# avr_ring2_v1_1.net
KiCad netlist of a schematic drawn in EAGLE
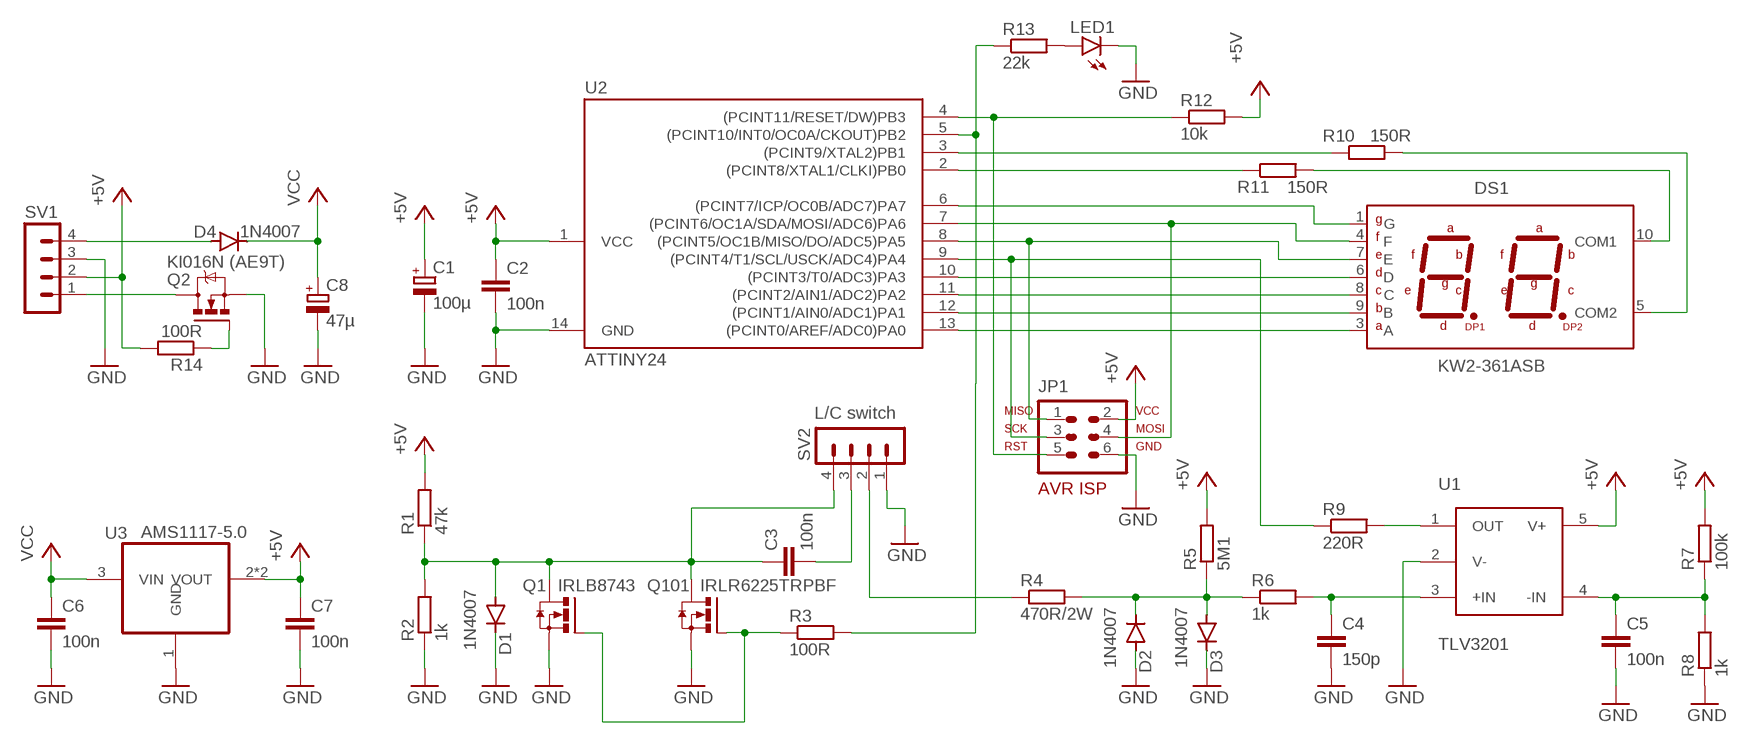
[diagram p0: schematic, sheet 1]

(export (version "E")
  (design (tool "Eeschema 10.0.6"))
  (components
    (comp (ref "C1")
      (value "100µ")
      (footprint "eagle-import:E2,5-5")
      (libsource (lib "eagle-import") (part "CPOL-EUE2.5-5"))
    )
    (comp (ref "C2")
      (value "100n")
      (footprint "eagle-import:C1206")
      (libsource (lib "eagle-import") (part "C-EUC1206"))
    )
    (comp (ref "C3")
      (value "100n")
      (footprint "eagle-import:C102_152-062X184")
      (libsource (lib "eagle-import") (part "C-EU102_152-062X184"))
    )
    (comp (ref "C4")
      (value "150p")
      (footprint "eagle-import:C1206")
      (libsource (lib "eagle-import") (part "C-EUC1206"))
    )
    (comp (ref "C5")
      (value "100n")
      (footprint "eagle-import:C1206")
      (libsource (lib "eagle-import") (part "C-EUC1206"))
    )
    (comp (ref "C6")
      (value "100n")
      (footprint "eagle-import:C1206")
      (libsource (lib "eagle-import") (part "C-EUC1206"))
    )
    (comp (ref "C7")
      (value "100n")
      (footprint "eagle-import:C1206")
      (libsource (lib "eagle-import") (part "C-EUC1206"))
    )
    (comp (ref "C8")
      (value "47µ")
      (footprint "eagle-import:E2,5-5")
      (libsource (lib "eagle-import") (part "CPOL-EUE2.5-5"))
    )
    (comp (ref "D1")
      (value "1N4007")
      (footprint "eagle-import:DO214AC")
      (libsource (lib "eagle-import") (part "DIODE-DO214AC"))
    )
    (comp (ref "D2")
      (value "1N4007")
      (footprint "eagle-import:DO214AC")
      (libsource (lib "eagle-import") (part "DIODE-DO214AC"))
    )
    (comp (ref "D3")
      (value "1N4007")
      (footprint "eagle-import:DO214AC")
      (libsource (lib "eagle-import") (part "DIODE-DO214AC"))
    )
    (comp (ref "D4")
      (value "1N4007")
      (footprint "eagle-import:DO214AC")
      (libsource (lib "eagle-import") (part "DIODE-DO214AC"))
    )
    (comp (ref "DS1")
      (value "KW2-361ASB")
      (footprint "eagle-import:DA03-11SURKWA")
      (fields (field (name "MANUFACTURER") "Kingbright") (field (name "MPN") "DA03-11SURKWA"))
      (libsource (lib "eagle-import") (part "DA03-11SUR-GA"))
    )
    (comp (ref "JP1")
      (value "AVR-ISP")
      (footprint "eagle-import:AVR-ISP-6")
      (libsource (lib "eagle-import") (part "AVR-ISP-6VERT"))
    )
    (comp (ref "LED1")
      (value "LED3MM")
      (footprint "eagle-import:LED3MM")
      (libsource (lib "eagle-import") (part "LED3MM"))
    )
    (comp (ref "Q1")
      (value "IRLB8743")
      (footprint "eagle-import:TO220AH")
      (libsource (lib "eagle-import") (part "IRF3704"))
    )
    (comp (ref "Q2")
      (value "KI016N (AE9T)")
      (footprint "eagle-import:SOT23")
      (libsource (lib "eagle-import") (part "NMOSFETSOT23-GSD_"))
    )
    (comp (ref "Q101")
      (value "IRLR6225TRPBF")
      (footprint "eagle-import:TO-252-3")
      (libsource (lib "eagle-import") (part "IRLR6225TRPBF"))
    )
    (comp (ref "R1")
      (value "47k")
      (footprint "eagle-import:R1206")
      (libsource (lib "eagle-import") (part "R-EU_R1206"))
    )
    (comp (ref "R2")
      (value "1k")
      (footprint "eagle-import:R1206")
      (libsource (lib "eagle-import") (part "R-EU_R1206"))
    )
    (comp (ref "R3")
      (value "100R")
      (footprint "eagle-import:R1206")
      (libsource (lib "eagle-import") (part "R-EU_R1206"))
    )
    (comp (ref "R4")
      (value "470R/2W")
      (footprint "eagle-import:0414_15")
      (libsource (lib "eagle-import") (part "R-EU_0414/15"))
    )
    (comp (ref "R5")
      (value "5M1")
      (footprint "eagle-import:R1206")
      (libsource (lib "eagle-import") (part "R-EU_R1206"))
    )
    (comp (ref "R6")
      (value "1k")
      (footprint "eagle-import:R1206")
      (libsource (lib "eagle-import") (part "R-EU_R1206"))
    )
    (comp (ref "R7")
      (value "100k")
      (footprint "eagle-import:R1206")
      (libsource (lib "eagle-import") (part "R-EU_R1206"))
    )
    (comp (ref "R8")
      (value "1k")
      (footprint "eagle-import:R1206")
      (libsource (lib "eagle-import") (part "R-EU_R1206"))
    )
    (comp (ref "R9")
      (value "220R")
      (footprint "eagle-import:R1206")
      (libsource (lib "eagle-import") (part "R-EU_R1206"))
    )
    (comp (ref "R10")
      (value "150R")
      (footprint "eagle-import:R1206")
      (libsource (lib "eagle-import") (part "R-EU_R1206"))
    )
    (comp (ref "R11")
      (value "150R")
      (footprint "eagle-import:R1206")
      (libsource (lib "eagle-import") (part "R-EU_R1206"))
    )
    (comp (ref "R12")
      (value "10k")
      (footprint "eagle-import:R1206")
      (libsource (lib "eagle-import") (part "R-EU_R1206"))
    )
    (comp (ref "R13")
      (value "22k")
      (footprint "eagle-import:R1206")
      (libsource (lib "eagle-import") (part "R-EU_R1206"))
    )
    (comp (ref "R14")
      (value "100R")
      (footprint "eagle-import:R1206")
      (libsource (lib "eagle-import") (part "R-EU_R1206"))
    )
    (comp (ref "SV1")
      (value "MA04-1")
      (footprint "eagle-import:MA04-1")
      (libsource (lib "eagle-import") (part "MA04-1"))
    )
    (comp (ref "SV2")
      (value "L/C switch")
      (footprint "eagle-import:MA04-1")
      (libsource (lib "eagle-import") (part "MA04-1"))
    )
    (comp (ref "U1")
      (value "TLV3201")
      (footprint "eagle-import:SOT-23-5")
      (fields
        (field (name "DIGIKEY_PART_NUMBER") "296-19546-1-ND")
        (field (name "MANUFACTURER") "Texas Instruments")
        (field (name "MPN") "OPA333AIDBVT")
        (field (name "CREATED") "PCBLayout.com")
      )
      (libsource (lib "eagle-import") (part "OPA333AIDBVT"))
    )
    (comp (ref "U2")
      (value "ATTINY24")
      (footprint "eagle-import:SOIC14")
      (libsource (lib "eagle-import") (part "TINY24/44/84-SSU"))
    )
    (comp (ref "U3")
      (value "AMS1117-5.0")
      (footprint "eagle-import:SOT223")
      (fields (field (name "MPN") "REG1117"))
      (libsource (lib "eagle-import") (part "REG1117"))
    )
  )
  (nets
    (net (code "1") (name "+5V") (class "Default")
      (node (ref "C1") (pin "+") (pinfunction "+_+") (pintype "passive"))
      (node (ref "C2") (pin "1") (pinfunction "1_1") (pintype "passive"))
      (node (ref "C7") (pin "1") (pinfunction "1_1") (pintype "passive"))
      (node (ref "JP1") (pin "2") (pinfunction "2_2") (pintype "passive"))
      (node (ref "R1") (pin "2") (pinfunction "2_2") (pintype "passive"))
      (node (ref "R12") (pin "2") (pinfunction "2_2") (pintype "passive"))
      (node (ref "R14") (pin "2") (pinfunction "2_2") (pintype "passive"))
      (node (ref "R5") (pin "2") (pinfunction "2_2") (pintype "passive"))
      (node (ref "R7") (pin "2") (pinfunction "2_2") (pintype "passive"))
      (node (ref "SV1") (pin "2") (pinfunction "2_2") (pintype "passive"))
      (node (ref "U1") (pin "5") (pinfunction "V+_5") (pintype "power_in"))
      (node (ref "U2") (pin "1") (pinfunction "VCC_1") (pintype "power_in"))
      (node (ref "U3") (pin "2") (pinfunction "VOUT_2") (pintype "output"))
      (node (ref "U3") (pin "4") (pinfunction "VOUT_4") (pintype "output"))
    )
    (net (code "2") (name "GND") (class "Default")
      (node (ref "C1") (pin "-") (pinfunction "-_-") (pintype "passive"))
      (node (ref "C2") (pin "2") (pinfunction "2_2") (pintype "passive"))
      (node (ref "C4") (pin "2") (pinfunction "2_2") (pintype "passive"))
      (node (ref "C5") (pin "2") (pinfunction "2_2") (pintype "passive"))
      (node (ref "C6") (pin "2") (pinfunction "2_2") (pintype "passive"))
      (node (ref "C7") (pin "2") (pinfunction "2_2") (pintype "passive"))
      (node (ref "C8") (pin "-") (pinfunction "-_-") (pintype "passive"))
      (node (ref "D1") (pin "C") (pinfunction "C_C") (pintype "passive"))
      (node (ref "D2") (pin "A") (pinfunction "A_A") (pintype "passive"))
      (node (ref "D3") (pin "C") (pinfunction "C_C") (pintype "passive"))
      (node (ref "JP1") (pin "6") (pinfunction "6_6") (pintype "passive"))
      (node (ref "LED1") (pin "K") (pinfunction "C_K") (pintype "passive"))
      (node (ref "Q1") (pin "E") (pinfunction "S_E") (pintype "passive"))
      (node (ref "Q101") (pin "2") (pinfunction "S_2") (pintype "passive"))
      (node (ref "Q2") (pin "2") (pinfunction "S_2") (pintype "passive"))
      (node (ref "R2") (pin "1") (pinfunction "1_1") (pintype "passive"))
      (node (ref "R8") (pin "1") (pinfunction "1_1") (pintype "passive"))
      (node (ref "SV1") (pin "3") (pinfunction "3_3") (pintype "passive"))
      (node (ref "SV2") (pin "1") (pinfunction "1_1") (pintype "passive"))
      (node (ref "U1") (pin "2") (pinfunction "V-_2") (pintype "power_in"))
      (node (ref "U2") (pin "14") (pinfunction "GND_14") (pintype "power_in"))
      (node (ref "U3") (pin "1") (pinfunction "GND_1") (pintype "power_in"))
    )
    (net (code "3") (name "Net-(C3-2-Pad3)") (class "Default")
      (node (ref "C3") (pin "2") (pinfunction "2_2") (pintype "passive"))
      (node (ref "C3") (pin "3") (pinfunction "2_3") (pintype "passive"))
      (node (ref "SV2") (pin "3") (pinfunction "3_3") (pintype "passive"))
    )
    (net (code "4") (name "Net-(D2-PadC)") (class "Default")
      (node (ref "D2") (pin "C") (pinfunction "C_C") (pintype "passive"))
      (node (ref "D3") (pin "A") (pinfunction "A_A") (pintype "passive"))
      (node (ref "R4") (pin "2") (pinfunction "2_2") (pintype "passive"))
      (node (ref "R5") (pin "1") (pinfunction "1_1") (pintype "passive"))
      (node (ref "R6") (pin "1") (pinfunction "1_1") (pintype "passive"))
    )
    (net (code "5") (name "Net-(D4-PadA)") (class "Default")
      (node (ref "D4") (pin "A") (pinfunction "A_A") (pintype "passive"))
      (node (ref "SV1") (pin "4") (pinfunction "4_4") (pintype "passive"))
    )
    (net (code "6") (name "Net-(DS1-A)") (class "Default")
      (node (ref "DS1") (pin "3") (pinfunction "A_3") (pintype "passive"))
      (node (ref "U2") (pin "13") (pinfunction "(PCINT0/AREF/ADC0)PA0_13") (pintype "bidirectional"))
    )
    (net (code "7") (name "Net-(DS1-B)") (class "Default")
      (node (ref "DS1") (pin "9") (pinfunction "B_9") (pintype "passive"))
      (node (ref "U2") (pin "12") (pinfunction "(PCINT1/AIN0/ADC1)PA1_12") (pintype "bidirectional"))
    )
    (net (code "8") (name "Net-(DS1-C)") (class "Default")
      (node (ref "DS1") (pin "8") (pinfunction "C_8") (pintype "passive"))
      (node (ref "U2") (pin "11") (pinfunction "(PCINT2/AIN1/ADC2)PA2_11") (pintype "bidirectional"))
    )
    (net (code "9") (name "Net-(DS1-COM1)") (class "Default")
      (node (ref "DS1") (pin "10") (pinfunction "COM1_10") (pintype "passive"))
      (node (ref "R11") (pin "2") (pinfunction "2_2") (pintype "passive"))
    )
    (net (code "10") (name "Net-(DS1-COM2)") (class "Default")
      (node (ref "DS1") (pin "5") (pinfunction "COM2_5") (pintype "passive"))
      (node (ref "R10") (pin "2") (pinfunction "2_2") (pintype "passive"))
    )
    (net (code "11") (name "Net-(DS1-D)") (class "Default")
      (node (ref "DS1") (pin "6") (pinfunction "D_6") (pintype "passive"))
      (node (ref "U2") (pin "10") (pinfunction "(PCINT3/T0/ADC3)PA3_10") (pintype "bidirectional"))
    )
    (net (code "12") (name "Net-(DS1-E)") (class "Default")
      (node (ref "DS1") (pin "7") (pinfunction "E_7") (pintype "passive"))
      (node (ref "JP1") (pin "1") (pinfunction "1_1") (pintype "passive"))
      (node (ref "U2") (pin "8") (pinfunction "(PCINT5/OC1B/MISO/DO/ADC5)PA5_8") (pintype "bidirectional"))
    )
    (net (code "13") (name "Net-(DS1-F)") (class "Default")
      (node (ref "DS1") (pin "4") (pinfunction "F_4") (pintype "passive"))
      (node (ref "JP1") (pin "4") (pinfunction "4_4") (pintype "passive"))
      (node (ref "U2") (pin "7") (pinfunction "(PCINT6/OC1A/SDA/MOSI/ADC6)PA6_7") (pintype "bidirectional"))
    )
    (net (code "14") (name "Net-(DS1-G)") (class "Default")
      (node (ref "DS1") (pin "1") (pinfunction "G_1") (pintype "passive"))
      (node (ref "U2") (pin "6") (pinfunction "(PCINT7/ICP/OC0B/ADC7)PA7_6") (pintype "bidirectional"))
    )
    (net (code "15") (name "Net-(LED1-PadA)") (class "Default")
      (node (ref "LED1") (pin "A") (pinfunction "A_A") (pintype "passive"))
      (node (ref "R13") (pin "2") (pinfunction "2_2") (pintype "passive"))
    )
    (net (code "16") (name "Net-(Q1-D)") (class "Default")
      (node (ref "C3") (pin "1") (pinfunction "1_1") (pintype "passive"))
      (node (ref "D1") (pin "A") (pinfunction "A_A") (pintype "passive"))
      (node (ref "Q1") (pin "C") (pinfunction "D_C") (pintype "passive"))
      (node (ref "Q101") (pin "3") (pinfunction "D_3") (pintype "passive"))
      (node (ref "R1") (pin "1") (pinfunction "1_1") (pintype "passive"))
      (node (ref "R2") (pin "2") (pinfunction "2_2") (pintype "passive"))
      (node (ref "SV2") (pin "4") (pinfunction "4_4") (pintype "passive"))
    )
    (net (code "17") (name "Net-(Q1-G)") (class "Default")
      (node (ref "Q1") (pin "B") (pinfunction "G_B") (pintype "passive"))
      (node (ref "Q101") (pin "1") (pinfunction "G_1") (pintype "passive"))
      (node (ref "R3") (pin "1") (pinfunction "1_1") (pintype "passive"))
    )
    (net (code "18") (name "Net-(Q2-D)") (class "Default")
      (node (ref "Q2") (pin "3") (pinfunction "D_3") (pintype "passive"))
      (node (ref "SV1") (pin "1") (pinfunction "1_1") (pintype "passive"))
    )
    (net (code "19") (name "Net-(Q2-G)") (class "Default")
      (node (ref "Q2") (pin "1") (pinfunction "G_1") (pintype "passive"))
      (node (ref "R14") (pin "1") (pinfunction "1_1") (pintype "passive"))
    )
    (net (code "20") (name "Net-(R4-Pad1)") (class "Default")
      (node (ref "R4") (pin "1") (pinfunction "1_1") (pintype "passive"))
      (node (ref "SV2") (pin "2") (pinfunction "2_2") (pintype "passive"))
    )
    (net (code "21") (name "Net-(U1-+IN)") (class "Default")
      (node (ref "C4") (pin "1") (pinfunction "1_1") (pintype "passive"))
      (node (ref "R6") (pin "2") (pinfunction "2_2") (pintype "passive"))
      (node (ref "U1") (pin "3") (pinfunction "+IN_3") (pintype "input"))
    )
    (net (code "22") (name "Net-(U1--IN)") (class "Default")
      (node (ref "C5") (pin "1") (pinfunction "1_1") (pintype "passive"))
      (node (ref "R7") (pin "1") (pinfunction "1_1") (pintype "passive"))
      (node (ref "R8") (pin "2") (pinfunction "2_2") (pintype "passive"))
      (node (ref "U1") (pin "4") (pinfunction "-IN_4") (pintype "input"))
    )
    (net (code "23") (name "Net-(U1-OUT)") (class "Default")
      (node (ref "R9") (pin "2") (pinfunction "2_2") (pintype "passive"))
      (node (ref "U1") (pin "1") (pinfunction "OUT_1") (pintype "output"))
    )
    (net (code "24") (name "Net-(U2-(PCINT4{slash}T1{slash}SCL{slash}USCK{slash}ADC4)PA4)") (class "Default")
      (node (ref "JP1") (pin "3") (pinfunction "3_3") (pintype "passive"))
      (node (ref "R9") (pin "1") (pinfunction "1_1") (pintype "passive"))
      (node (ref "U2") (pin "9") (pinfunction "(PCINT4/T1/SCL/USCK/ADC4)PA4_9") (pintype "bidirectional"))
    )
    (net (code "25") (name "Net-(U2-(PCINT8{slash}XTAL1{slash}CLKI)PB0)") (class "Default")
      (node (ref "R11") (pin "1") (pinfunction "1_1") (pintype "passive"))
      (node (ref "U2") (pin "2") (pinfunction "(PCINT8/XTAL1/CLKI)PB0_2") (pintype "bidirectional"))
    )
    (net (code "26") (name "Net-(U2-(PCINT9{slash}XTAL2)PB1)") (class "Default")
      (node (ref "R10") (pin "1") (pinfunction "1_1") (pintype "passive"))
      (node (ref "U2") (pin "3") (pinfunction "(PCINT9/XTAL2)PB1_3") (pintype "bidirectional"))
    )
    (net (code "27") (name "Net-(U2-(PCINT10{slash}INT0{slash}OC0A{slash}CKOUT)PB2)") (class "Default")
      (node (ref "R13") (pin "1") (pinfunction "1_1") (pintype "passive"))
      (node (ref "R3") (pin "2") (pinfunction "2_2") (pintype "passive"))
      (node (ref "U2") (pin "5") (pinfunction "(PCINT10/INT0/OC0A/CKOUT)PB2_5") (pintype "bidirectional"))
    )
    (net (code "28") (name "Net-(U2-(PCINT11{slash}RESET{slash}DW)PB3)") (class "Default")
      (node (ref "JP1") (pin "5") (pinfunction "5_5") (pintype "passive"))
      (node (ref "R12") (pin "1") (pinfunction "1_1") (pintype "passive"))
      (node (ref "U2") (pin "4") (pinfunction "(PCINT11/RESET/DW)PB3_4") (pintype "bidirectional"))
    )
    (net (code "29") (name "VCC") (class "Default")
      (node (ref "C6") (pin "1") (pinfunction "1_1") (pintype "passive"))
      (node (ref "C8") (pin "+") (pinfunction "+_+") (pintype "passive"))
      (node (ref "D4") (pin "C") (pinfunction "C_C") (pintype "passive"))
      (node (ref "U3") (pin "3") (pinfunction "VIN_3") (pintype "input"))
    )
  )
)
